# Soldeerbord.net
KiCad netlist of a schematic drawn in Altium Designer
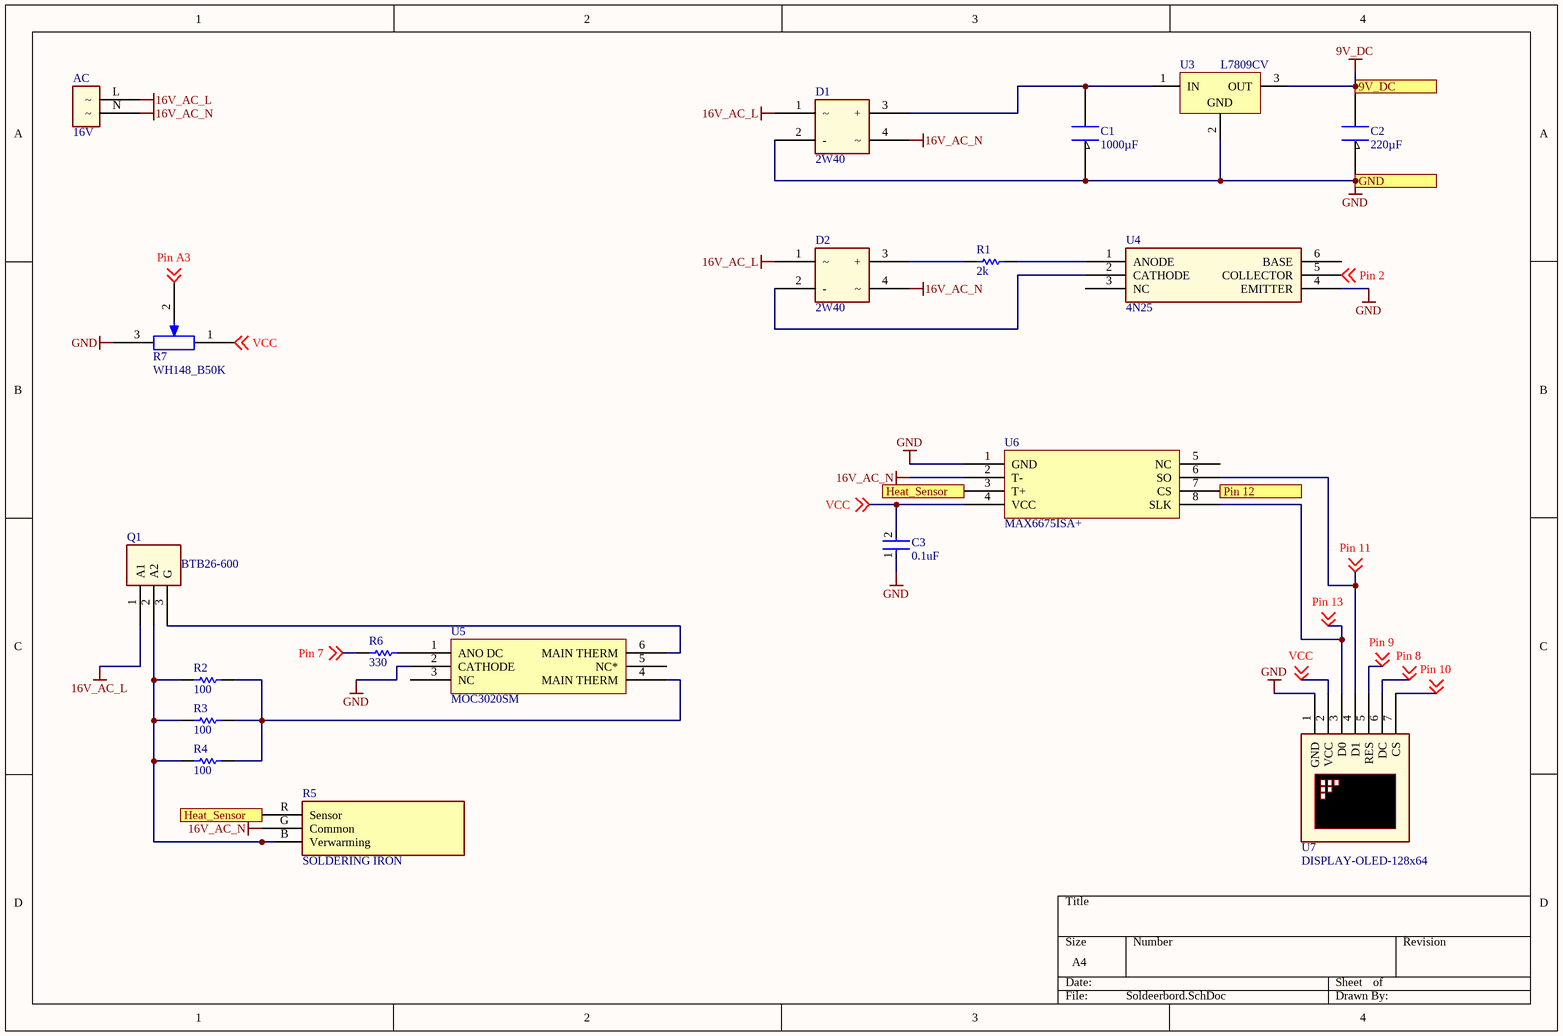
[diagram p0: Soldeerbord.SchDoc]

(export (version "E")
  (design (tool "Eeschema 10.0.6"))
  (components
    (comp (ref "AC")
      (value "16V")
      (footprint "PCB_Voeding_16V_AC")
      (libsource (lib "test") (part "Voeding_16V_AC"))
    )
    (comp (ref "C1")
      (value "1000µF")
      (footprint "PCB-Capasitor")
      (libsource (lib "soldeerLibrary") (part "Capasitor"))
    )
    (comp (ref "C2")
      (value "220µF")
      (footprint "PCB-Capasitor")
      (libsource (lib "soldeerLibrary") (part "Capasitor"))
    )
    (comp (ref "C3")
      (value "0.1uF")
      (footprint "FP-GRM188-0_1-e0_2_0_55-IPC_A")
      (description "Chip Multilayer Ceramic Capacitors for General Purpose, 0603, 10uF, X5R, 15%, 20%, 6.3V")
      (fields (field (name "VOLTAGE") "6.3V") (field (name "TOLERANCE") "20%"))
      (libsource (lib "Altium Content Vault") (part "02cd4be3c70576c341d710602a673aa"))
    )
    (comp (ref "D1") (value "2W40") (footprint "PCB_2W40") (libsource (lib "soldeerLibrary") (part "2W40")))
    (comp (ref "D2") (value "2W40") (footprint "PCB_2W40") (libsource (lib "soldeerLibrary") (part "2W40")))
    (comp (ref "Q1")
      (value "BTB26-600")
      (footprint "BTB26-600B")
      (libsource (lib "2W10") (part "BTB26-600B"))
    )
    (comp (ref "R1")
      (value "2k")
      (footprint "RESC2013X50X30LL20T20")
      (fields (field (name "MANUFACTURER") "Vishay Dale") (field (name "PART NUMBER") "CRCW08050000Z0EA"))
      (libsource (lib "Altium Content Vault") (part "RES"))
    )
    (comp (ref "R2")
      (value "100")
      (footprint "RESC2013X50X30LL20T20")
      (fields (field (name "MANUFACTURER") "Vishay Dale") (field (name "PART NUMBER") "CRCW08050000Z0EA"))
      (libsource (lib "Altium Content Vault") (part "RES"))
    )
    (comp (ref "R3")
      (value "100")
      (footprint "RESC2013X50X30LL20T20")
      (fields (field (name "MANUFACTURER") "Vishay Dale") (field (name "PART NUMBER") "CRCW08050000Z0EA"))
      (libsource (lib "Altium Content Vault") (part "RES"))
    )
    (comp (ref "R4")
      (value "100")
      (footprint "RESC2013X50X30LL20T20")
      (fields (field (name "MANUFACTURER") "Vishay Dale") (field (name "PART NUMBER") "CRCW08050000Z0EA"))
      (libsource (lib "Altium Content Vault") (part "RES"))
    )
    (comp (ref "R5")
      (value "SOLDERING IRON")
      (footprint "PCB_Soldering_Iron")
      (libsource (lib "2W10") (part "Soldering_Iron"))
    )
    (comp (ref "R6")
      (value "330")
      (footprint "RESC2013X50X30LL20T20")
      (fields (field (name "MANUFACTURER") "Vishay Dale") (field (name "PART NUMBER") "CRCW08050000Z0EA"))
      (libsource (lib "Altium Content Vault") (part "RES"))
    )
    (comp (ref "R7")
      (value "WH148_B50K")
      (footprint "PCBC_WH148_B50K")
      (libsource (lib "2W10") (part "WH148_B50K"))
    )
    (comp (ref "U3")
      (value "L7809CV")
      (footprint "TO220")
      (description "Positive Voltage Regulator, 24V, 3-Pin TO-220")
      (libsource (lib "Altium Content Vault") (part "PM-REG-L4940-SIL3"))
    )
    (comp (ref "U4") (value "4N25") (footprint "4N25-300E") (libsource (lib "2W10") (part "4N25-300E")))
    (comp (ref "U5")
      (value "MOC3020SM")
      (footprint "SOP254P920X508-6N")
      (libsource (lib "2W10") (part "MOC3020SM"))
    )
    (comp (ref "U6")
      (value "MAX6675ISA+")
      (footprint "SOP127P600X175-8N")
      (libsource (lib "2W10") (part "MAX6675ISA+"))
    )
    (comp (ref "U7")
      (value "DISPLAY-OLED-128x64")
      (footprint "PCB_SPI_OLED_7pin")
      (libsource (lib "2W10") (part "SPI_OLED_7Pin"))
    )
  )
  (nets
    (net (code "1") (name "/Heat_Sensor") (class "Default")
      (node (ref "R5") (pin "R") (pinfunction "Sensor_R") (pintype "passive"))
      (node (ref "U6") (pin "3") (pinfunction "T+_3") (pintype "passive"))
    )
    (net (code "2") (name "/Pin 12") (class "Default")
      (node (ref "U6") (pin "7") (pinfunction "CS_7") (pintype "passive"))
    )
    (net (code "3") (name "9V_DC") (class "Default")
      (node (ref "C2") (pin "1") (pintype "passive"))
      (node (ref "U3") (pin "3") (pinfunction "OUT_3") (pintype "power_in"))
    )
    (net (code "4") (name "16V_AC_L") (class "Default")
      (node (ref "AC") (pin "L") (pinfunction "~_L") (pintype "passive"))
      (node (ref "D1") (pin "1") (pinfunction "~_1") (pintype "passive"))
      (node (ref "D2") (pin "1") (pinfunction "~_1") (pintype "passive"))
      (node (ref "Q1") (pin "1") (pinfunction "A1_1") (pintype "passive"))
    )
    (net (code "5") (name "16V_AC_N") (class "Default")
      (node (ref "AC") (pin "N") (pinfunction "~_N") (pintype "passive"))
      (node (ref "D1") (pin "4") (pinfunction "~_4") (pintype "passive"))
      (node (ref "D2") (pin "4") (pinfunction "~_4") (pintype "passive"))
      (node (ref "R5") (pin "G") (pinfunction "Common_G") (pintype "passive"))
      (node (ref "U6") (pin "2") (pinfunction "T-_2") (pintype "passive"))
    )
    (net (code "6") (name "GND") (class "Default")
      (node (ref "C1") (pin "2") (pintype "passive"))
      (node (ref "C2") (pin "2") (pintype "passive"))
      (node (ref "C3") (pin "1") (pinfunction "1_1") (pintype "passive"))
      (node (ref "D1") (pin "2") (pinfunction "-_2") (pintype "passive"))
      (node (ref "R7") (pin "3") (pintype "passive"))
      (node (ref "U3") (pin "2") (pinfunction "GND_2") (pintype "power_in"))
      (node (ref "U4") (pin "4") (pinfunction "EMITTER_4") (pintype "passive"))
      (node (ref "U5") (pin "2") (pinfunction "CATHODE_2") (pintype "passive"))
      (node (ref "U6") (pin "1") (pinfunction "GND_1") (pintype "passive"))
      (node (ref "U7") (pin "1") (pinfunction "GND_1") (pintype "passive"))
    )
    (net (code "7") (name "Net-(D1-+)") (class "Default")
      (node (ref "C1") (pin "1") (pintype "passive"))
      (node (ref "D1") (pin "3") (pinfunction "+_3") (pintype "passive"))
      (node (ref "U3") (pin "1") (pinfunction "IN_1") (pintype "power_in"))
    )
    (net (code "8") (name "Net-(D2-+)") (class "Default")
      (node (ref "D2") (pin "3") (pinfunction "+_3") (pintype "passive"))
      (node (ref "R1") (pin "1") (pinfunction "1_1") (pintype "passive"))
    )
    (net (code "9") (name "Net-(D2--)") (class "Default")
      (node (ref "D2") (pin "2") (pinfunction "-_2") (pintype "passive"))
      (node (ref "U4") (pin "2") (pinfunction "CATHODE_2") (pintype "passive"))
    )
    (net (code "10") (name "Net-(Q1-A2)") (class "Default")
      (node (ref "Q1") (pin "2") (pinfunction "A2_2") (pintype "passive"))
      (node (ref "R2") (pin "1") (pinfunction "1_1") (pintype "passive"))
      (node (ref "R3") (pin "1") (pinfunction "1_1") (pintype "passive"))
      (node (ref "R4") (pin "1") (pinfunction "1_1") (pintype "passive"))
      (node (ref "R5") (pin "B") (pinfunction "Verwarming_B") (pintype "passive"))
    )
    (net (code "11") (name "Net-(Q1-G)") (class "Default")
      (node (ref "Q1") (pin "3") (pinfunction "G_3") (pintype "passive"))
      (node (ref "U5") (pin "6") (pinfunction "MAIN_THERM_6") (pintype "passive"))
    )
    (net (code "12") (name "Net-(R2-Pad2)") (class "Default")
      (node (ref "R2") (pin "2") (pinfunction "2_2") (pintype "passive"))
      (node (ref "R3") (pin "2") (pinfunction "2_2") (pintype "passive"))
      (node (ref "R4") (pin "2") (pinfunction "2_2") (pintype "passive"))
      (node (ref "U5") (pin "4") (pinfunction "MAIN_THERM_4") (pintype "passive"))
    )
    (net (code "13") (name "Net-(U4-ANODE)") (class "Default")
      (node (ref "R1") (pin "2") (pinfunction "2_2") (pintype "passive"))
      (node (ref "U4") (pin "1") (pinfunction "ANODE_1") (pintype "passive"))
    )
    (net (code "14") (name "Net-(U5-ANO_DC)") (class "Default")
      (node (ref "R6") (pin "2") (pinfunction "2_2") (pintype "passive"))
      (node (ref "U5") (pin "1") (pinfunction "ANO_DC_1") (pintype "passive"))
    )
    (net (code "15") (name "Pin 2") (class "Default")
      (node (ref "U4") (pin "5") (pinfunction "COLLECTOR_5") (pintype "passive"))
    )
    (net (code "16") (name "Pin 7") (class "Default")
      (node (ref "R6") (pin "1") (pinfunction "1_1") (pintype "passive"))
    )
    (net (code "17") (name "Pin 8") (class "Default")
      (node (ref "U7") (pin "6") (pinfunction "DC_6") (pintype "passive"))
    )
    (net (code "18") (name "Pin 9") (class "Default")
      (node (ref "U7") (pin "5") (pinfunction "RES_5") (pintype "passive"))
    )
    (net (code "19") (name "Pin 10") (class "Default")
      (node (ref "U7") (pin "7") (pinfunction "CS_7") (pintype "passive"))
    )
    (net (code "20") (name "Pin 11") (class "Default")
      (node (ref "U6") (pin "6") (pinfunction "SO_6") (pintype "passive"))
      (node (ref "U7") (pin "4") (pinfunction "D1_4") (pintype "passive"))
    )
    (net (code "21") (name "Pin 13") (class "Default")
      (node (ref "U6") (pin "8") (pinfunction "SLK_8") (pintype "passive"))
      (node (ref "U7") (pin "3") (pinfunction "D0_3") (pintype "passive"))
    )
    (net (code "22") (name "Pin A3") (class "Default") (node (ref "R7") (pin "2") (pintype "passive")))
    (net (code "23") (name "VCC") (class "Default")
      (node (ref "C3") (pin "2") (pinfunction "2_2") (pintype "passive"))
      (node (ref "R7") (pin "1") (pintype "passive"))
      (node (ref "U6") (pin "4") (pinfunction "VCC_4") (pintype "passive"))
      (node (ref "U7") (pin "2") (pinfunction "VCC_2") (pintype "passive"))
    )
    (net (code "24") (name "unconnected-(U4-BASE-Pad6)") (class "Default")
      (node (ref "U4") (pin "6") (pinfunction "BASE_6") (pintype "passive"))
    )
    (net (code "25") (name "unconnected-(U4-NC-Pad3)") (class "Default")
      (node (ref "U4") (pin "3") (pinfunction "NC_3") (pintype "passive"))
    )
    (net (code "26") (name "unconnected-(U5-NC*-Pad5)") (class "Default")
      (node (ref "U5") (pin "5") (pinfunction "NC*_5") (pintype "passive"))
    )
    (net (code "27") (name "unconnected-(U5-NC-Pad3)") (class "Default")
      (node (ref "U5") (pin "3") (pinfunction "NC_3") (pintype "passive"))
    )
    (net (code "28") (name "unconnected-(U6-NC-Pad5)") (class "Default")
      (node (ref "U6") (pin "5") (pinfunction "NC_5") (pintype "passive"))
    )
  )
)
